# 3V3_LDO_Regulator.net
KiCad netlist of a schematic drawn in Altium Designer
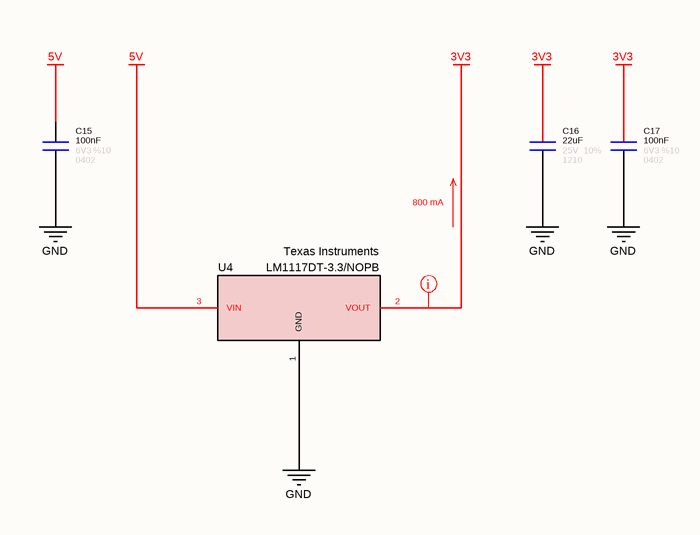
[diagram p0: 3V3 LDO Regulator.SchDoc]

(export (version "E")
  (design (tool "Eeschema 10.0.6"))
  (components
    (comp (ref "C15")
      (value "100nF")
      (footprint "CAPACITOR_0402")
      (description "Capacitor - 100nF [0402-6V3] (Ceramic)")
      (fields
        (field (name "MANUFACTURER PART NUMBER") "04026D104KAT4A")
        (field (name "TOLERANCE") "%10")
        (field (name "VOLTAGE") "6V3")
        (field (name "CASE") "0402")
        (field (name "Comment") "Capacitor - 100nF [0402] (Ceramic)")
      )
      (libsource (lib "Akkoyun") (part "Capacitor - 100nF [0402-6V3]"))
    )
    (comp (ref "C16")
      (value "22uF")
      (footprint "CAPACITOR_0603")
      (description "Multilayer Ceramic Capacitors MLCC - SMD/SMT 22UF 25V 10% 1210")
      (fields
        (field (name "MANUFACTURER PART NUMBER") "GRM32ER71E226KE15L")
        (field (name "TOLERANCE") "10%")
        (field (name "CASE") "1210")
        (field (name "VOLTAGE") "25V")
        (field (name "Comment") "Capacitor - 22uF [1210] (Ceramic)")
      )
      (libsource (lib "Akkoyun") (part "Capacitor - 22uF [1210-6V3]"))
    )
    (comp (ref "C17")
      (value "100nF")
      (footprint "CAPACITOR_0402")
      (description "Capacitor - 100nF [0402-6V3] (Ceramic)")
      (fields
        (field (name "MANUFACTURER PART NUMBER") "04026D104KAT4A")
        (field (name "TOLERANCE") "%10")
        (field (name "VOLTAGE") "6V3")
        (field (name "CASE") "0402")
        (field (name "Comment") "Capacitor - 100nF [0402] (Ceramic)")
      )
      (libsource (lib "Akkoyun") (part "Capacitor - 100nF [0402-6V3]"))
    )
    (comp (ref "U4")
      (value "LDO Regulator")
      (footprint "TO-252")
      (description "LDO Voltage Regulators 800MA LDO LINEAR REG")
      (fields
        (field (name "MANUFACTURER PART NUMBER") "LM1117DT-3.3/NOPB")
        (field (name "MANUFACTURER NAME") "Texas Instruments")
      )
      (libsource (lib "Akkoyun") (part "IC - LM1117DT-3.3/NOPB"))
    )
  )
  (nets
    (net (code "1") (name "3V3") (class "Default")
      (node (ref "C16") (pin "2") (pinfunction "2_2") (pintype "passive"))
      (node (ref "C17") (pin "2") (pinfunction "2_2") (pintype "passive"))
      (node (ref "U4") (pin "2") (pinfunction "VOUT_2") (pintype "power_in"))
    )
    (net (code "2") (name "5V") (class "Default")
      (node (ref "C15") (pin "2") (pinfunction "2_2") (pintype "passive"))
      (node (ref "U4") (pin "3") (pinfunction "VIN_3") (pintype "power_in"))
    )
    (net (code "3") (name "GND") (class "Default")
      (node (ref "C15") (pin "1") (pinfunction "1_1") (pintype "passive"))
      (node (ref "C16") (pin "1") (pinfunction "1_1") (pintype "passive"))
      (node (ref "C17") (pin "1") (pinfunction "1_1") (pintype "passive"))
      (node (ref "U4") (pin "1") (pinfunction "GND_1") (pintype "power_in"))
    )
  )
)
